# UI.net
KiCad netlist of a schematic drawn in Altium Designer
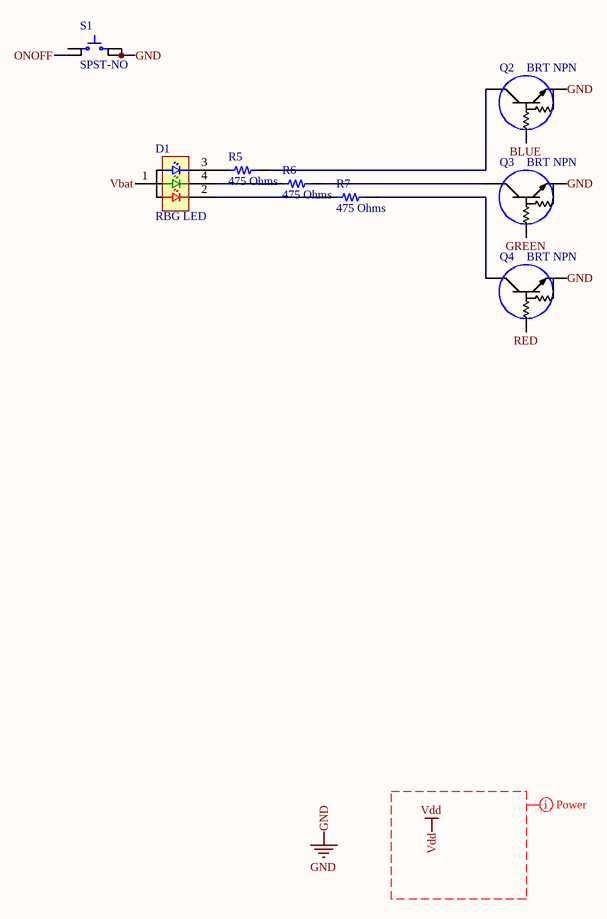
[diagram p0: UI.SchDoc]

(export (version "E")
  (design (tool "Eeschema 10.0.6"))
  (components
    (comp (ref "D1")
      (value "RBG LED")
      (footprint "LED 0101/0404 RGB")
      (description "LED 0404 RBG")
      (fields (field (name "PART NUMBER") "SML-LX0404SIUPGUSB") (field (name "MANUFACTURER") "Lumex"))
      (libsource (lib "ekuore-library") (part "LED RBG"))
    )
    (comp (ref "Q2")
      (value "BRT NPN")
      (footprint "ON SEMI SOT-416")
      (description "TRANS PREBIAS NPN 200MW SC75")
      (fields (field (name "PART NUMBER") "DTC114EET1G") (field (name "MANUFACTURER") "ON Semiconductor"))
      (libsource (lib "ekuore-library") (part "BRT NPN SOT-23-3"))
    )
    (comp (ref "Q3")
      (value "BRT NPN")
      (footprint "ON SEMI SOT-416")
      (description "TRANS PREBIAS NPN 200MW SC75")
      (fields (field (name "PART NUMBER") "DTC114EET1G") (field (name "MANUFACTURER") "ON Semiconductor"))
      (libsource (lib "ekuore-library") (part "BRT NPN SOT-23-3"))
    )
    (comp (ref "Q4")
      (value "BRT NPN")
      (footprint "ON SEMI SOT-416")
      (description "TRANS PREBIAS NPN 200MW SC75")
      (fields (field (name "PART NUMBER") "DTC114EET1G") (field (name "MANUFACTURER") "ON Semiconductor"))
      (libsource (lib "ekuore-library") (part "BRT NPN SOT-23-3"))
    )
    (comp (ref "R5")
      (value "475 Ohms")
      (footprint "RES 0201_0603")
      (description "RES SMD 475 OHM 1% 1/20W 0201")
      (fields (field (name "PART NUMBER") "CRCW0201475RFKED") (field (name "MANUFACTURER") "Vishay Dale"))
      (libsource (lib "Celestial Altium Library") (part "Resistor"))
    )
    (comp (ref "R6")
      (value "475 Ohms")
      (footprint "RES 0201_0603")
      (description "RES SMD 475 OHM 1% 1/20W 0201")
      (fields (field (name "PART NUMBER") "CRCW0201475RFKED") (field (name "MANUFACTURER") "Vishay Dale"))
      (libsource (lib "Celestial Altium Library") (part "Resistor"))
    )
    (comp (ref "R7")
      (value "475 Ohms")
      (footprint "RES 0201_0603")
      (description "RES SMD 475 OHM 1% 1/20W 0201")
      (fields (field (name "PART NUMBER") "CRCW0201475RFKED") (field (name "MANUFACTURER") "Vishay Dale"))
      (libsource (lib "Celestial Altium Library") (part "Resistor"))
    )
    (comp (ref "S1")
      (value "SPST-NO")
      (footprint "Panasonic evqp7")
      (description "Switch Tactile N.O. SPST Right Angle 0.05A 12V")
      (fields (field (name "PART NUMBER") "EVQ-P7A01P") (field (name "MANUFACTURER") "Panasonic"))
      (libsource (lib "ekuore-library") (part "SPST-NO 4 PIN"))
    )
  )
  (nets
    (net (code "1") (name "/BLUE") (class "Default")
      (node (ref "Q2") (pin "1") (pinfunction "B_1") (pintype "passive"))
    )
    (net (code "2") (name "/GREEN") (class "Default")
      (node (ref "Q3") (pin "1") (pinfunction "B_1") (pintype "passive"))
    )
    (net (code "3") (name "/ONOFF") (class "Default")
      (node (ref "S1") (pin "1'") (pinfunction "1'_1'") (pintype "passive"))
    )
    (net (code "4") (name "/RED") (class "Default")
      (node (ref "Q4") (pin "1") (pinfunction "B_1") (pintype "passive"))
    )
    (net (code "5") (name "/Vbat") (class "Default")
      (node (ref "D1") (pin "1") (pinfunction "A_1") (pintype "passive"))
    )
    (net (code "6") (name "GND") (class "Default")
      (node (ref "Q2") (pin "2") (pinfunction "E_2") (pintype "passive"))
      (node (ref "Q3") (pin "2") (pinfunction "E_2") (pintype "passive"))
      (node (ref "Q4") (pin "2") (pinfunction "E_2") (pintype "passive"))
      (node (ref "S1") (pin "2") (pinfunction "2_2") (pintype "passive"))
      (node (ref "S1") (pin "2'") (pinfunction "2'_2'") (pintype "passive"))
    )
    (net (code "7") (name "Net-(D1-C2)") (class "Default")
      (node (ref "D1") (pin "2") (pinfunction "C2_2") (pintype "passive"))
      (node (ref "R7") (pin "1") (pinfunction "1_1") (pintype "passive"))
    )
    (net (code "8") (name "Net-(D1-C3)") (class "Default")
      (node (ref "D1") (pin "3") (pinfunction "C3_3") (pintype "passive"))
      (node (ref "R5") (pin "1") (pinfunction "1_1") (pintype "passive"))
    )
    (net (code "9") (name "Net-(D1-C4)") (class "Default")
      (node (ref "D1") (pin "4") (pinfunction "C4_4") (pintype "passive"))
      (node (ref "R6") (pin "1") (pinfunction "1_1") (pintype "passive"))
    )
    (net (code "10") (name "Net-(Q2-C)") (class "Default")
      (node (ref "Q2") (pin "3") (pinfunction "C_3") (pintype "passive"))
      (node (ref "R5") (pin "2") (pinfunction "2_2") (pintype "passive"))
    )
    (net (code "11") (name "Net-(Q3-C)") (class "Default")
      (node (ref "Q3") (pin "3") (pinfunction "C_3") (pintype "passive"))
      (node (ref "R6") (pin "2") (pinfunction "2_2") (pintype "passive"))
    )
    (net (code "12") (name "Net-(Q4-C)") (class "Default")
      (node (ref "Q4") (pin "3") (pinfunction "C_3") (pintype "passive"))
      (node (ref "R7") (pin "2") (pinfunction "2_2") (pintype "passive"))
    )
    (net (code "14") (name "unconnected-(S1-Pad1)") (class "Default")
      (node (ref "S1") (pin "1") (pinfunction "1_1") (pintype "passive"))
    )
  )
)
